# PLL.net
KiCad netlist of a schematic drawn in Altium Designer
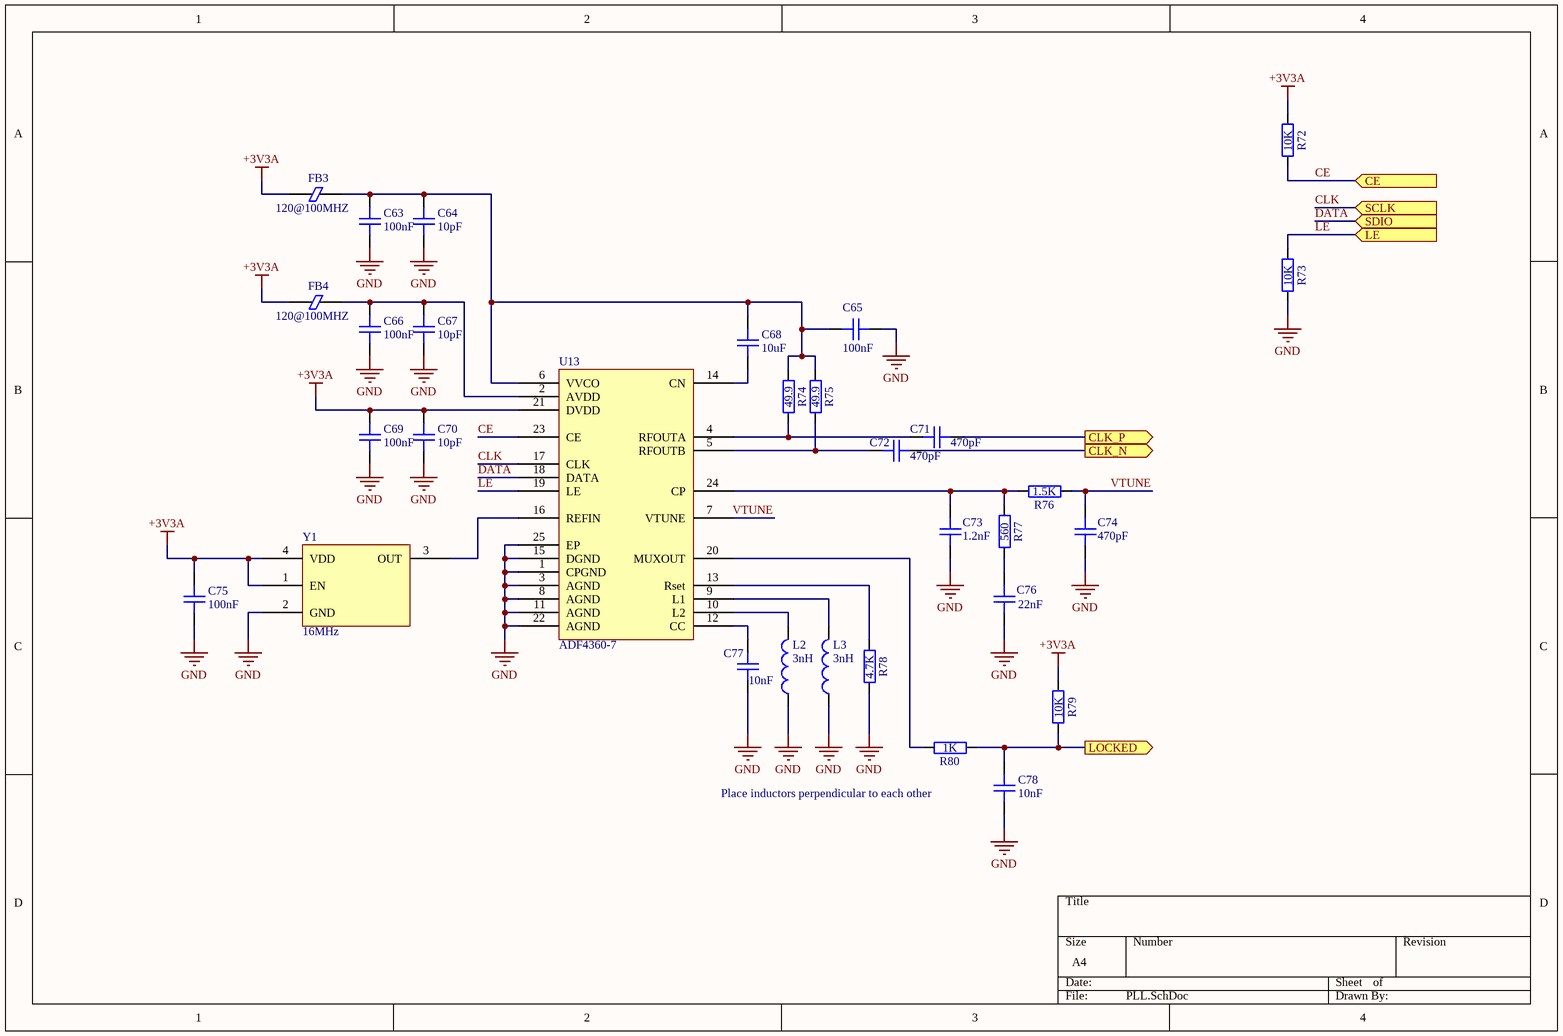
[diagram p0: PLL.SchDoc]

(export (version "E")
  (design (tool "Eeschema 10.0.6"))
  (components
    (comp (ref "C63")
      (value "100nF")
      (footprint "GEN_C_0402")
      (libsource (lib "DSO") (part "CAP 100nF 16V X7R 0402"))
    )
    (comp (ref "C64")
      (value "10pF")
      (footprint "GEN_C_0402")
      (libsource (lib "DSO") (part "CAP 10pF 50V C0G 0402"))
    )
    (comp (ref "C65")
      (value "100nF")
      (footprint "GEN_C_0402")
      (libsource (lib "DSO") (part "CAP 100nF 16V X7R 0402"))
    )
    (comp (ref "C66")
      (value "100nF")
      (footprint "GEN_C_0402")
      (libsource (lib "DSO") (part "CAP 100nF 16V X7R 0402"))
    )
    (comp (ref "C67")
      (value "10pF")
      (footprint "GEN_C_0402")
      (libsource (lib "DSO") (part "CAP 10pF 50V C0G 0402"))
    )
    (comp (ref "C68")
      (value "10uF")
      (footprint "GEN_C_0603")
      (libsource (lib "DSO") (part "CAP 10uF 10V X5R 0603"))
    )
    (comp (ref "C69")
      (value "100nF")
      (footprint "GEN_C_0402")
      (libsource (lib "DSO") (part "CAP 100nF 16V X7R 0402"))
    )
    (comp (ref "C70")
      (value "10pF")
      (footprint "GEN_C_0402")
      (libsource (lib "DSO") (part "CAP 10pF 50V C0G 0402"))
    )
    (comp (ref "C71")
      (value "470pF")
      (footprint "GEN_C_0402")
      (libsource (lib "DSO") (part "CAP 470pF 50V C0G 0402"))
    )
    (comp (ref "C72")
      (value "470pF")
      (footprint "GEN_C_0402")
      (libsource (lib "DSO") (part "CAP 470pF 50V C0G 0402"))
    )
    (comp (ref "C73")
      (value "1.2nF")
      (footprint "GEN_C_0603")
      (libsource (lib "DSO") (part "CAP 1.2nF 50V C0G 0603"))
    )
    (comp (ref "C74")
      (value "470pF")
      (footprint "GEN_C_0402")
      (libsource (lib "DSO") (part "CAP 470pF 50V C0G 0402"))
    )
    (comp (ref "C75")
      (value "100nF")
      (footprint "GEN_C_0402")
      (libsource (lib "DSO") (part "CAP 100nF 16V X7R 0402"))
    )
    (comp (ref "C76")
      (value "22nF")
      (footprint "GEN_C_0603")
      (libsource (lib "DSO") (part "CAP 22nF 100V X7R 0603"))
    )
    (comp (ref "C77")
      (value "10nF")
      (footprint "GEN_C_0402")
      (libsource (lib "DSO") (part "CAP 10nF 50V X7R 0402"))
    )
    (comp (ref "C78")
      (value "10nF")
      (footprint "GEN_C_0402")
      (libsource (lib "DSO") (part "CAP 10nF 50V X7R 0402"))
    )
    (comp (ref "FB3")
      (value "120@100MHZ")
      (footprint "GEN_R_0402")
      (libsource (lib "DSO") (part "FERRITE BEAD 120 OHM 0402"))
    )
    (comp (ref "FB4")
      (value "120@100MHZ")
      (footprint "GEN_R_0402")
      (libsource (lib "DSO") (part "FERRITE BEAD 120 OHM 0402"))
    )
    (comp (ref "L2")
      (value "3nH")
      (footprint "GEN_L_0402")
      (libsource (lib "DSO") (part "IND 3nH +/-0.05nH 0402"))
    )
    (comp (ref "L3")
      (value "3nH")
      (footprint "GEN_L_0402")
      (libsource (lib "DSO") (part "IND 3nH +/-0.05nH 0402"))
    )
    (comp (ref "R72")
      (value "10K")
      (footprint "GEN_R_0402")
      (fields (field (name "TOLERANCE") "1%"))
      (libsource (lib "DSO") (part "RES 10K OHM 1% 1/10W 0402"))
    )
    (comp (ref "R73")
      (value "10K")
      (footprint "GEN_R_0402")
      (fields (field (name "TOLERANCE") "1%"))
      (libsource (lib "DSO") (part "RES 10K OHM 1% 1/10W 0402"))
    )
    (comp (ref "R74")
      (value "49.9")
      (footprint "GEN_R_0402")
      (fields (field (name "TOLERANCE") "1%"))
      (libsource (lib "DSO") (part "RES 49.9 OHM 1% 1/10W 0402"))
    )
    (comp (ref "R75")
      (value "49.9")
      (footprint "GEN_R_0402")
      (fields (field (name "TOLERANCE") "1%"))
      (libsource (lib "DSO") (part "RES 49.9 OHM 1% 1/10W 0402"))
    )
    (comp (ref "R76")
      (value "1.5K")
      (footprint "GEN_R_0402")
      (fields (field (name "TOLERANCE") "1%"))
      (libsource (lib "DSO") (part "RES 1.5K OHM 1% 1/16W 0402"))
    )
    (comp (ref "R77")
      (value "560")
      (footprint "GEN_R_0402")
      (fields (field (name "TOLERANCE") "1%"))
      (libsource (lib "DSO") (part "RES 560 OHM 1% 1/16W 0402"))
    )
    (comp (ref "R78")
      (value "4.7K")
      (footprint "GEN_R_0402")
      (fields (field (name "TOLERANCE") "1%"))
      (libsource (lib "DSO") (part "RES 4.7K OHM 1% 1/10W 0402"))
    )
    (comp (ref "R79")
      (value "10K")
      (footprint "GEN_R_0402")
      (fields (field (name "TOLERANCE") "1%"))
      (libsource (lib "DSO") (part "RES 10K OHM 1% 1/10W 0402"))
    )
    (comp (ref "R80")
      (value "1K")
      (footprint "GEN_R_0402")
      (fields (field (name "TOLERANCE") "1%"))
      (libsource (lib "DSO") (part "RES 1K OHM 1% 1/10W 0402"))
    )
    (comp (ref "U13")
      (value "ADF4360-7")
      (footprint "AD_QFN24_CP-24-14")
      (libsource (lib "DSO") (part "IC PLL ADF4360-7"))
    )
    (comp (ref "Y1")
      (value "16MHz")
      (footprint "ECS_TXO-2016")
      (libsource (lib "DSO") (part "OSC 16MHz ECS-TXO-2016"))
    )
  )
  (nets
    (net (code "1") (name "+3V3A") (class "Default")
      (node (ref "C69") (pin "2") (pinfunction "2_2") (pintype "passive"))
      (node (ref "C70") (pin "2") (pinfunction "2_2") (pintype "passive"))
      (node (ref "C75") (pin "1") (pinfunction "1_1") (pintype "passive"))
      (node (ref "FB3") (pin "1") (pinfunction "1_1") (pintype "passive"))
      (node (ref "FB4") (pin "1") (pinfunction "1_1") (pintype "passive"))
      (node (ref "R72") (pin "1") (pinfunction "1_1") (pintype "passive"))
      (node (ref "R79") (pin "1") (pinfunction "1_1") (pintype "passive"))
      (node (ref "U13") (pin "21") (pinfunction "DVDD_21") (pintype "passive"))
      (node (ref "Y1") (pin "1") (pinfunction "EN_1") (pintype "passive"))
      (node (ref "Y1") (pin "4") (pinfunction "VDD_4") (pintype "power_in"))
    )
    (net (code "2") (name "/CE") (class "Default")
      (node (ref "R72") (pin "2") (pinfunction "2_2") (pintype "passive"))
      (node (ref "U13") (pin "23") (pinfunction "CE_23") (pintype "passive"))
    )
    (net (code "3") (name "/CLK") (class "Default")
      (node (ref "U13") (pin "17") (pinfunction "CLK_17") (pintype "passive"))
    )
    (net (code "4") (name "/CLK_N") (class "Default")
      (node (ref "C72") (pin "1") (pinfunction "1_1") (pintype "passive"))
    )
    (net (code "5") (name "/CLK_P") (class "Default")
      (node (ref "C71") (pin "1") (pinfunction "1_1") (pintype "passive"))
    )
    (net (code "6") (name "/DATA") (class "Default")
      (node (ref "U13") (pin "18") (pinfunction "DATA_18") (pintype "passive"))
    )
    (net (code "7") (name "/LE") (class "Default")
      (node (ref "R73") (pin "1") (pinfunction "1_1") (pintype "passive"))
      (node (ref "U13") (pin "19") (pinfunction "LE_19") (pintype "passive"))
    )
    (net (code "8") (name "/LOCKED") (class "Default")
      (node (ref "C78") (pin "2") (pinfunction "2_2") (pintype "passive"))
      (node (ref "R79") (pin "2") (pinfunction "2_2") (pintype "passive"))
      (node (ref "R80") (pin "2") (pinfunction "2_2") (pintype "passive"))
    )
    (net (code "9") (name "/VTUNE") (class "Default")
      (node (ref "C74") (pin "2") (pinfunction "2_2") (pintype "passive"))
      (node (ref "R76") (pin "2") (pinfunction "2_2") (pintype "passive"))
      (node (ref "U13") (pin "7") (pinfunction "VTUNE_7") (pintype "passive"))
    )
    (net (code "10") (name "GND") (class "Default")
      (node (ref "C63") (pin "1") (pinfunction "1_1") (pintype "passive"))
      (node (ref "C64") (pin "1") (pinfunction "1_1") (pintype "passive"))
      (node (ref "C65") (pin "1") (pinfunction "1_1") (pintype "passive"))
      (node (ref "C66") (pin "1") (pinfunction "1_1") (pintype "passive"))
      (node (ref "C67") (pin "1") (pinfunction "1_1") (pintype "passive"))
      (node (ref "C69") (pin "1") (pinfunction "1_1") (pintype "passive"))
      (node (ref "C70") (pin "1") (pinfunction "1_1") (pintype "passive"))
      (node (ref "C73") (pin "1") (pinfunction "1_1") (pintype "passive"))
      (node (ref "C74") (pin "1") (pinfunction "1_1") (pintype "passive"))
      (node (ref "C75") (pin "2") (pinfunction "2_2") (pintype "passive"))
      (node (ref "C76") (pin "1") (pinfunction "1_1") (pintype "passive"))
      (node (ref "C77") (pin "1") (pinfunction "1_1") (pintype "passive"))
      (node (ref "C78") (pin "1") (pinfunction "1_1") (pintype "passive"))
      (node (ref "L2") (pin "1") (pinfunction "1_1") (pintype "passive"))
      (node (ref "L3") (pin "1") (pinfunction "1_1") (pintype "passive"))
      (node (ref "R73") (pin "2") (pinfunction "2_2") (pintype "passive"))
      (node (ref "R78") (pin "1") (pinfunction "1_1") (pintype "passive"))
      (node (ref "U13") (pin "1") (pinfunction "CPGND_1") (pintype "power_in"))
      (node (ref "U13") (pin "11") (pinfunction "AGND_11") (pintype "passive"))
      (node (ref "U13") (pin "15") (pinfunction "DGND_15") (pintype "passive"))
      (node (ref "U13") (pin "22") (pinfunction "AGND_22") (pintype "passive"))
      (node (ref "U13") (pin "25") (pinfunction "EP_25") (pintype "passive"))
      (node (ref "U13") (pin "3") (pinfunction "AGND_3") (pintype "passive"))
      (node (ref "U13") (pin "8") (pinfunction "AGND_8") (pintype "passive"))
      (node (ref "Y1") (pin "2") (pinfunction "GND_2") (pintype "power_in"))
    )
    (net (code "11") (name "Net-(C76-Pad2)") (class "Default")
      (node (ref "C76") (pin "2") (pinfunction "2_2") (pintype "passive"))
      (node (ref "R77") (pin "1") (pinfunction "1_1") (pintype "passive"))
    )
    (net (code "12") (name "Net-(U13-AVDD)") (class "Default")
      (node (ref "C66") (pin "2") (pinfunction "2_2") (pintype "passive"))
      (node (ref "C67") (pin "2") (pinfunction "2_2") (pintype "passive"))
      (node (ref "FB4") (pin "2") (pinfunction "2_2") (pintype "passive"))
      (node (ref "U13") (pin "2") (pinfunction "AVDD_2") (pintype "passive"))
    )
    (net (code "13") (name "Net-(U13-CC)") (class "Default")
      (node (ref "C77") (pin "2") (pinfunction "2_2") (pintype "passive"))
      (node (ref "U13") (pin "12") (pinfunction "CC_12") (pintype "passive"))
    )
    (net (code "14") (name "Net-(U13-CN)") (class "Default")
      (node (ref "C68") (pin "1") (pinfunction "1_1") (pintype "passive"))
      (node (ref "U13") (pin "14") (pinfunction "CN_14") (pintype "passive"))
    )
    (net (code "15") (name "Net-(U13-CP)") (class "Default")
      (node (ref "C73") (pin "2") (pinfunction "2_2") (pintype "passive"))
      (node (ref "R76") (pin "1") (pinfunction "1_1") (pintype "passive"))
      (node (ref "R77") (pin "2") (pinfunction "2_2") (pintype "passive"))
      (node (ref "U13") (pin "24") (pinfunction "CP_24") (pintype "passive"))
    )
    (net (code "16") (name "Net-(U13-L1)") (class "Default")
      (node (ref "L3") (pin "2") (pinfunction "2_2") (pintype "passive"))
      (node (ref "U13") (pin "9") (pinfunction "L1_9") (pintype "passive"))
    )
    (net (code "17") (name "Net-(U13-L2)") (class "Default")
      (node (ref "L2") (pin "2") (pinfunction "2_2") (pintype "passive"))
      (node (ref "U13") (pin "10") (pinfunction "L2_10") (pintype "passive"))
    )
    (net (code "18") (name "Net-(U13-MUXOUT)") (class "Default")
      (node (ref "R80") (pin "1") (pinfunction "1_1") (pintype "passive"))
      (node (ref "U13") (pin "20") (pinfunction "MUXOUT_20") (pintype "passive"))
    )
    (net (code "19") (name "Net-(U13-REFIN)") (class "Default")
      (node (ref "U13") (pin "16") (pinfunction "REFIN_16") (pintype "passive"))
      (node (ref "Y1") (pin "3") (pinfunction "OUT_3") (pintype "passive"))
    )
    (net (code "20") (name "Net-(U13-RFOUTA)") (class "Default")
      (node (ref "C71") (pin "2") (pinfunction "2_2") (pintype "passive"))
      (node (ref "R74") (pin "1") (pinfunction "1_1") (pintype "passive"))
      (node (ref "U13") (pin "4") (pinfunction "RFOUTA_4") (pintype "passive"))
    )
    (net (code "21") (name "Net-(U13-RFOUTB)") (class "Default")
      (node (ref "C72") (pin "2") (pinfunction "2_2") (pintype "passive"))
      (node (ref "R75") (pin "1") (pinfunction "1_1") (pintype "passive"))
      (node (ref "U13") (pin "5") (pinfunction "RFOUTB_5") (pintype "passive"))
    )
    (net (code "22") (name "Net-(U13-Rset)") (class "Default")
      (node (ref "R78") (pin "2") (pinfunction "2_2") (pintype "passive"))
      (node (ref "U13") (pin "13") (pinfunction "Rset_13") (pintype "passive"))
    )
    (net (code "23") (name "Net-(U13-VVCO)") (class "Default")
      (node (ref "C63") (pin "2") (pinfunction "2_2") (pintype "passive"))
      (node (ref "C64") (pin "2") (pinfunction "2_2") (pintype "passive"))
      (node (ref "C65") (pin "2") (pinfunction "2_2") (pintype "passive"))
      (node (ref "C68") (pin "2") (pinfunction "2_2") (pintype "passive"))
      (node (ref "FB3") (pin "2") (pinfunction "2_2") (pintype "passive"))
      (node (ref "R74") (pin "2") (pinfunction "2_2") (pintype "passive"))
      (node (ref "R75") (pin "2") (pinfunction "2_2") (pintype "passive"))
      (node (ref "U13") (pin "6") (pinfunction "VVCO_6") (pintype "passive"))
    )
  )
)
